# Sheet1.net
KiCad netlist of a schematic drawn in Altium Designer
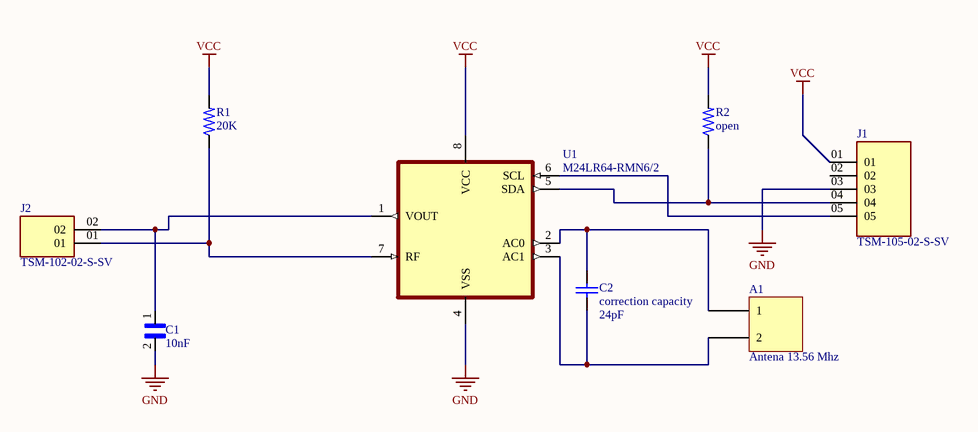
[diagram p0: Sheet1.SchDoc]

(export (version "E")
  (design (tool "Eeschema 10.0.6"))
  (components
    (comp (ref "A1")
      (value "Antena 13.56 Mhz")
      (footprint "pcb_antenna")
      (description "Antenna 13.56 Mhz")
      (libsource (lib "Schlib1") (part "PCB_ANTENNA"))
    )
    (comp (ref "C1")
      (value "10nF")
      (footprint "PcbLib1:CAPC2012X140N")
      (description "Cap Ceramic 10nF")
      (fields (field (name "MP") "08053G334ZAT2A"))
      (libsource (lib "Schlib1") (part "08053G334ZAT2A"))
    )
    (comp (ref "C2")
      (value "correction capacity")
      (footprint "6-0805_M")
      (description "Capacitor")
      (fields (field (name "ALTIUM_VALUE") "24pF") (field (name "PUBLISHER") "Altium Limited"))
      (libsource (lib "Miscellaneous Devices") (part "Cap"))
    )
    (comp (ref "J1")
      (value "TSM-105-02-S-SV")
      (footprint "SAMTEC_TSM-105-02-S-SV")
      (description "Conn Unshrouded Header HDR 5 POS 2.54mm Solder ST SMD Tube")
      (fields (field (name "MF") "Samtec"))
      (libsource (lib "Schlib1") (part "TSM-105-02-S-SV"))
    )
    (comp (ref "J2")
      (value "TSM-102-02-S-SV")
      (footprint "SAMTEC_TSM-102-02-S-SV")
      (description "Conn Unshrouded Header HDR 2 POS 2.54mm Solder ST SMD T/R")
      (fields (field (name "MF") "Samtec Inc.") (field (name "MP") "TSM-102-02-S-SV-P-TR"))
      (libsource (lib "Schlib1") (part "TSM-102-02-S-SV"))
    )
    (comp (ref "R1")
      (value "20K")
      (footprint "PcbLib1:RESC2012X65N")
      (description "RN 0805 20K 0.1% 10PPM 1KRL")
      (fields (field (name "MP") "1676221-2"))
      (libsource (lib "Schlib1") (part "1676221-2"))
    )
    (comp (ref "R2")
      (value "open")
      (footprint "PcbLib1:RESC2012X65N")
      (fields (field (name "MP") "1676221-2"))
      (libsource (lib "Schlib1") (part "1676221-2"))
    )
    (comp (ref "U1")
      (value "M24LR64-RMN6/2")
      (footprint "SOIC127P600X175-8N")
      (description "64 Kbit EEPROM")
      (fields (field (name "MP") "M24LR64-RMN6-2"))
      (libsource (lib "Schlib1") (part "M24LR64-RMN6/2"))
    )
  )
  (nets
    (net (code "1") (name "GND") (class "Default")
      (node (ref "C1") (pin "2") (pinfunction "2_2") (pintype "passive"))
      (node (ref "J1") (pin "03") (pinfunction "03_03") (pintype "passive"))
      (node (ref "U1") (pin "4") (pinfunction "VSS_4") (pintype "power_in"))
    )
    (net (code "2") (name "Net-(U1-AC0)") (class "Default")
      (node (ref "A1") (pin "1") (pinfunction "1_1") (pintype "passive"))
      (node (ref "C2") (pin "2") (pinfunction "2_2") (pintype "passive"))
      (node (ref "U1") (pin "2") (pinfunction "AC0_2") (pintype "output"))
    )
    (net (code "3") (name "Net-(U1-AC1)") (class "Default")
      (node (ref "A1") (pin "2") (pinfunction "2_2") (pintype "passive"))
      (node (ref "C2") (pin "1") (pinfunction "1_1") (pintype "passive"))
      (node (ref "U1") (pin "3") (pinfunction "AC1_3") (pintype "output"))
    )
    (net (code "4") (name "Net-(U1-RF)") (class "Default")
      (node (ref "J2") (pin "01") (pinfunction "01_01") (pintype "passive"))
      (node (ref "R1") (pin "1") (pinfunction "1_1") (pintype "passive"))
      (node (ref "U1") (pin "7") (pinfunction "RF_7") (pintype "input"))
    )
    (net (code "5") (name "Net-(U1-SCL)") (class "Default")
      (node (ref "J1") (pin "05") (pinfunction "05_05") (pintype "passive"))
      (node (ref "U1") (pin "6") (pinfunction "SCL_6") (pintype "input"))
    )
    (net (code "6") (name "Net-(U1-SDA)") (class "Default")
      (node (ref "J1") (pin "04") (pinfunction "04_04") (pintype "passive"))
      (node (ref "R2") (pin "1") (pinfunction "1_1") (pintype "passive"))
      (node (ref "U1") (pin "5") (pinfunction "SDA_5") (pintype "output"))
    )
    (net (code "7") (name "Net-(U1-VOUT)") (class "Default")
      (node (ref "C1") (pin "1") (pinfunction "1_1") (pintype "passive"))
      (node (ref "J2") (pin "02") (pinfunction "02_02") (pintype "passive"))
      (node (ref "U1") (pin "1") (pinfunction "VOUT_1") (pintype "output"))
    )
    (net (code "8") (name "VCC") (class "Default")
      (node (ref "J1") (pin "01") (pinfunction "01_01") (pintype "passive"))
      (node (ref "R1") (pin "2") (pinfunction "2_2") (pintype "passive"))
      (node (ref "R2") (pin "2") (pinfunction "2_2") (pintype "passive"))
      (node (ref "U1") (pin "8") (pinfunction "VCC_8") (pintype "power_in"))
    )
    (net (code "9") (name "unconnected-(J1-Pad02)") (class "Default")
      (node (ref "J1") (pin "02") (pinfunction "02_02") (pintype "passive"))
    )
  )
)
